# Watch-It-Board-2.net
KiCad netlist of a schematic drawn in EAGLE
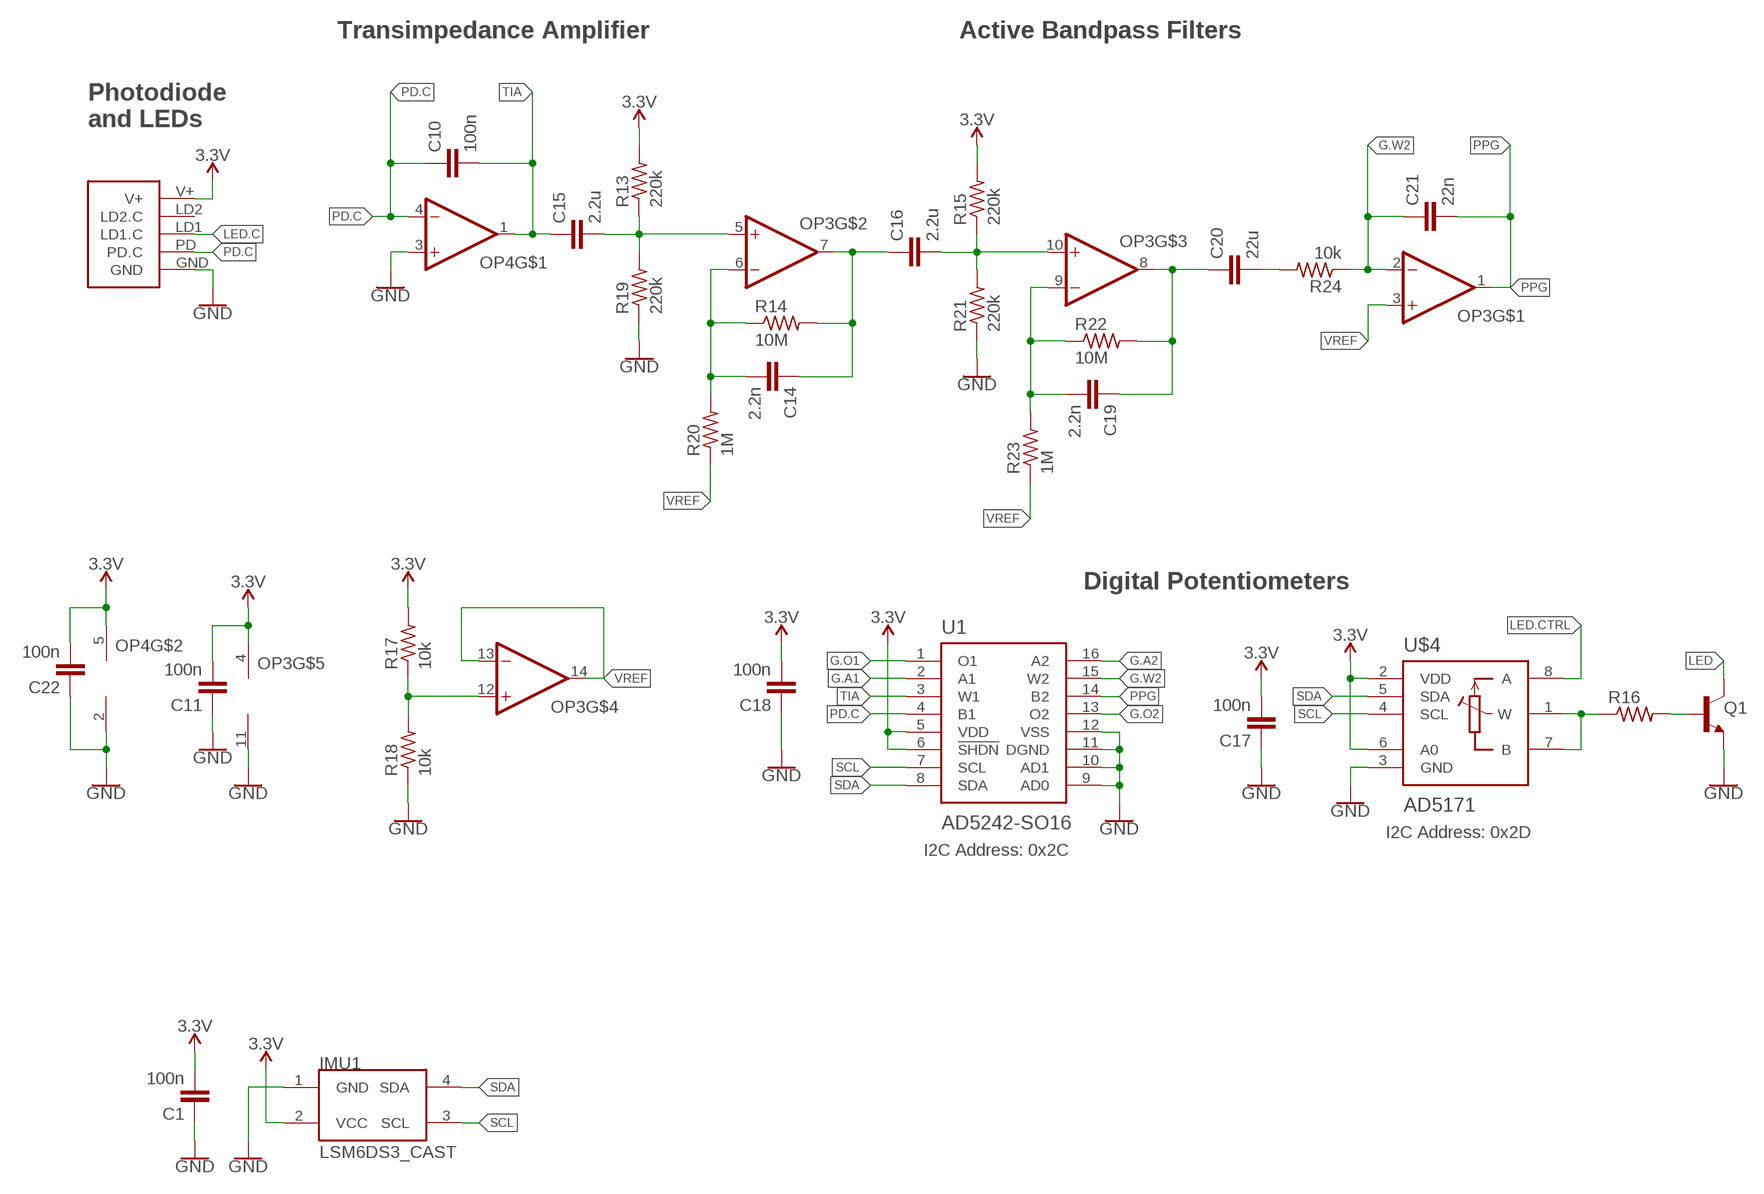
[diagram p0: schematic, sheet 1]

(export (version "E")
  (design (tool "Eeschema 10.0.6"))
  (components
    (comp (ref "C1")
      (value "100n")
      (footprint "eagle-import:C0603")
      (libsource (lib "eagle-import") (part "CAPACITOR0603"))
    )
    (comp (ref "C10")
      (value "100n")
      (footprint "eagle-import:C0603")
      (libsource (lib "eagle-import") (part "CAPACITOR0603"))
    )
    (comp (ref "C11")
      (value "100n")
      (footprint "eagle-import:C0603")
      (libsource (lib "eagle-import") (part "CAPACITOR0603"))
    )
    (comp (ref "C14")
      (value "2.2n")
      (footprint "eagle-import:C0603")
      (libsource (lib "eagle-import") (part "CAPACITOR0603"))
    )
    (comp (ref "C15")
      (value "2.2u")
      (footprint "eagle-import:C0603")
      (libsource (lib "eagle-import") (part "CAPACITOR0603"))
    )
    (comp (ref "C16")
      (value "2.2u")
      (footprint "eagle-import:C0603")
      (libsource (lib "eagle-import") (part "CAPACITOR0603"))
    )
    (comp (ref "C17")
      (value "100n")
      (footprint "eagle-import:C0603")
      (libsource (lib "eagle-import") (part "CAPACITOR0603"))
    )
    (comp (ref "C18")
      (value "100n")
      (footprint "eagle-import:C0603")
      (libsource (lib "eagle-import") (part "CAPACITOR0603"))
    )
    (comp (ref "C19")
      (value "2.2n")
      (footprint "eagle-import:C0603")
      (libsource (lib "eagle-import") (part "CAPACITOR0603"))
    )
    (comp (ref "C20")
      (value "22u")
      (footprint "eagle-import:C0603")
      (libsource (lib "eagle-import") (part "CAPACITOR0603"))
    )
    (comp (ref "C21")
      (value "22n")
      (footprint "eagle-import:C0603")
      (libsource (lib "eagle-import") (part "CAPACITOR0603"))
    )
    (comp (ref "C22")
      (value "100n")
      (footprint "eagle-import:C0603")
      (libsource (lib "eagle-import") (part "CAPACITOR0603"))
    )
    (comp (ref "IMU1")
      (value "LSM6DS3_CAST")
      (footprint "eagle-import:LSM6DS3_CAST")
      (libsource (lib "eagle-import") (part "LSM6DS3_CAST"))
    )
    (comp (ref "OP3")
      (value "OP-QUAD-SO14")
      (footprint "eagle-import:SO14")
      (libsource (lib "eagle-import") (part "OP-QUAD-SO14"))
    )
    (comp (ref "OP4")
      (value "OP-SINGLEOT")
      (footprint "eagle-import:SOT23-5")
      (libsource (lib "eagle-import") (part "OP-SINGLEOT"))
    )
    (comp (ref "Q1")
      (value "NPN-GENERIC")
      (footprint "eagle-import:SOT23-3")
      (libsource (lib "eagle-import") (part "NPN-GENERIC"))
    )
    (comp (ref "R13")
      (value "220k")
      (footprint "eagle-import:R0603")
      (libsource (lib "eagle-import") (part "RESISTOR0603"))
    )
    (comp (ref "R14")
      (value "10M")
      (footprint "eagle-import:R0603")
      (libsource (lib "eagle-import") (part "RESISTOR0603"))
    )
    (comp (ref "R15")
      (value "220k")
      (footprint "eagle-import:R0603")
      (libsource (lib "eagle-import") (part "RESISTOR0603"))
    )
    (comp (ref "R16")
      (value "RESISTOR0603")
      (footprint "eagle-import:R0603")
      (libsource (lib "eagle-import") (part "RESISTOR0603"))
    )
    (comp (ref "R17")
      (value "10k")
      (footprint "eagle-import:R0402")
      (libsource (lib "eagle-import") (part "RESISTOR0402"))
    )
    (comp (ref "R18")
      (value "10k")
      (footprint "eagle-import:R0402")
      (libsource (lib "eagle-import") (part "RESISTOR0402"))
    )
    (comp (ref "R19")
      (value "220k")
      (footprint "eagle-import:R0603")
      (libsource (lib "eagle-import") (part "RESISTOR0603"))
    )
    (comp (ref "R20")
      (value "1M")
      (footprint "eagle-import:R0603")
      (libsource (lib "eagle-import") (part "RESISTOR0603"))
    )
    (comp (ref "R21")
      (value "220k")
      (footprint "eagle-import:R0603")
      (libsource (lib "eagle-import") (part "RESISTOR0603"))
    )
    (comp (ref "R22")
      (value "10M")
      (footprint "eagle-import:R0603")
      (libsource (lib "eagle-import") (part "RESISTOR0603"))
    )
    (comp (ref "R23")
      (value "1M")
      (footprint "eagle-import:R0603")
      (libsource (lib "eagle-import") (part "RESISTOR0603"))
    )
    (comp (ref "R24")
      (value "10k")
      (footprint "eagle-import:R0603")
      (libsource (lib "eagle-import") (part "RESISTOR0603"))
    )
    (comp (ref "U$3")
      (value "PPG.MODULE.2")
      (footprint "eagle-import:PPG.MODULE.2")
      (libsource (lib "eagle-import") (part "PPG.MODULE.2"))
    )
    (comp (ref "U$4")
      (value "AD5171")
      (footprint "eagle-import:SOT-23-8")
      (libsource (lib "eagle-import") (part "AD5171"))
    )
    (comp (ref "U1")
      (value "AD5242-SO16")
      (footprint "eagle-import:SO16")
      (libsource (lib "eagle-import") (part "AD5242-SO16"))
    )
  )
  (nets
    (net (code "1") (name "3.3V") (class "Default")
      (node (ref "C1") (pin "2") (pinfunction "2_2") (pintype "passive"))
      (node (ref "C11") (pin "2") (pinfunction "2_2") (pintype "passive"))
      (node (ref "C17") (pin "2") (pinfunction "2_2") (pintype "passive"))
      (node (ref "C18") (pin "2") (pinfunction "2_2") (pintype "passive"))
      (node (ref "C22") (pin "2") (pinfunction "2_2") (pintype "passive"))
      (node (ref "IMU1") (pin "2") (pinfunction "VCC_2") (pintype "bidirectional"))
      (node (ref "OP3") (pin "4") (pinfunction "V+_4") (pintype "power_in"))
      (node (ref "OP4") (pin "5") (pinfunction "V+_5") (pintype "power_in"))
      (node (ref "R13") (pin "2") (pinfunction "2_2") (pintype "passive"))
      (node (ref "R15") (pin "2") (pinfunction "2_2") (pintype "passive"))
      (node (ref "R17") (pin "2") (pinfunction "2_2") (pintype "passive"))
      (node (ref "U$3") (pin "V+") (pinfunction "V+_V+") (pintype "bidirectional"))
      (node (ref "U$4") (pin "2") (pinfunction "VDD_2") (pintype "bidirectional"))
      (node (ref "U$4") (pin "6") (pinfunction "A0_6") (pintype "bidirectional"))
      (node (ref "U1") (pin "5") (pinfunction "VDD_5") (pintype "bidirectional"))
      (node (ref "U1") (pin "6") (pinfunction "~{SHDN}_6") (pintype "bidirectional"))
    )
    (net (code "2") (name "G.A1") (class "Default")
      (node (ref "U1") (pin "2") (pinfunction "A1_2") (pintype "bidirectional"))
    )
    (net (code "3") (name "G.A2") (class "Default")
      (node (ref "U1") (pin "16") (pinfunction "A2_16") (pintype "bidirectional"))
    )
    (net (code "4") (name "G.O1") (class "Default")
      (node (ref "U1") (pin "1") (pinfunction "O1_1") (pintype "bidirectional"))
    )
    (net (code "5") (name "G.O2") (class "Default")
      (node (ref "U1") (pin "13") (pinfunction "O2_13") (pintype "bidirectional"))
    )
    (net (code "6") (name "G.W2") (class "Default")
      (node (ref "C21") (pin "1") (pinfunction "1_1") (pintype "passive"))
      (node (ref "OP3") (pin "2") (pinfunction "-IN_2") (pintype "input"))
      (node (ref "R24") (pin "1") (pinfunction "1_1") (pintype "passive"))
      (node (ref "U1") (pin "15") (pinfunction "W2_15") (pintype "bidirectional"))
    )
    (net (code "7") (name "GND") (class "Default")
      (node (ref "C1") (pin "1") (pinfunction "1_1") (pintype "passive"))
      (node (ref "C11") (pin "1") (pinfunction "1_1") (pintype "passive"))
      (node (ref "C17") (pin "1") (pinfunction "1_1") (pintype "passive"))
      (node (ref "C18") (pin "1") (pinfunction "1_1") (pintype "passive"))
      (node (ref "C22") (pin "1") (pinfunction "1_1") (pintype "passive"))
      (node (ref "IMU1") (pin "1") (pinfunction "GND_1") (pintype "bidirectional"))
      (node (ref "OP3") (pin "11") (pinfunction "V-_11") (pintype "power_in"))
      (node (ref "OP4") (pin "2") (pinfunction "V-_2") (pintype "power_in"))
      (node (ref "OP4") (pin "3") (pinfunction "+IN_3") (pintype "input"))
      (node (ref "Q1") (pin "2") (pinfunction "E_2") (pintype "passive"))
      (node (ref "R18") (pin "1") (pinfunction "1_1") (pintype "passive"))
      (node (ref "R19") (pin "1") (pinfunction "1_1") (pintype "passive"))
      (node (ref "R21") (pin "1") (pinfunction "1_1") (pintype "passive"))
      (node (ref "U$3") (pin "GND") (pinfunction "GND_GND") (pintype "bidirectional"))
      (node (ref "U$4") (pin "3") (pinfunction "GND_3") (pintype "bidirectional"))
      (node (ref "U1") (pin "10") (pinfunction "AD1_10") (pintype "bidirectional"))
      (node (ref "U1") (pin "11") (pinfunction "DGND_11") (pintype "bidirectional"))
      (node (ref "U1") (pin "12") (pinfunction "VSS_12") (pintype "bidirectional"))
      (node (ref "U1") (pin "9") (pinfunction "AD0_9") (pintype "bidirectional"))
    )
    (net (code "8") (name "LED") (class "Default")
      (node (ref "Q1") (pin "3") (pinfunction "C_3") (pintype "passive"))
    )
    (net (code "9") (name "LED.C") (class "Default")
      (node (ref "U$3") (pin "LD1") (pinfunction "LD1.C_LD1") (pintype "bidirectional"))
    )
    (net (code "10") (name "LED.CTRL") (class "Default")
      (node (ref "U$4") (pin "8") (pinfunction "A_8") (pintype "bidirectional"))
    )
    (net (code "11") (name "Net-(C20-Pad2)") (class "Default")
      (node (ref "C20") (pin "2") (pinfunction "2_2") (pintype "passive"))
      (node (ref "R24") (pin "2") (pinfunction "2_2") (pintype "passive"))
    )
    (net (code "12") (name "Net-(OP3B-+IN)") (class "Default")
      (node (ref "C15") (pin "2") (pinfunction "2_2") (pintype "passive"))
      (node (ref "OP3") (pin "5") (pinfunction "+IN_5") (pintype "input"))
      (node (ref "R13") (pin "1") (pinfunction "1_1") (pintype "passive"))
      (node (ref "R19") (pin "2") (pinfunction "2_2") (pintype "passive"))
    )
    (net (code "13") (name "Net-(OP3B--IN)") (class "Default")
      (node (ref "C14") (pin "2") (pinfunction "2_2") (pintype "passive"))
      (node (ref "OP3") (pin "6") (pinfunction "-IN_6") (pintype "input"))
      (node (ref "R14") (pin "1") (pinfunction "1_1") (pintype "passive"))
      (node (ref "R20") (pin "2") (pinfunction "2_2") (pintype "passive"))
    )
    (net (code "14") (name "Net-(OP3B-OUT)") (class "Default")
      (node (ref "C14") (pin "1") (pinfunction "1_1") (pintype "passive"))
      (node (ref "C16") (pin "1") (pinfunction "1_1") (pintype "passive"))
      (node (ref "OP3") (pin "7") (pinfunction "OUT_7") (pintype "output"))
      (node (ref "R14") (pin "2") (pinfunction "2_2") (pintype "passive"))
    )
    (net (code "15") (name "Net-(OP3C-+IN)") (class "Default")
      (node (ref "C16") (pin "2") (pinfunction "2_2") (pintype "passive"))
      (node (ref "OP3") (pin "10") (pinfunction "+IN_10") (pintype "input"))
      (node (ref "R15") (pin "1") (pinfunction "1_1") (pintype "passive"))
      (node (ref "R21") (pin "2") (pinfunction "2_2") (pintype "passive"))
    )
    (net (code "16") (name "Net-(OP3C--IN)") (class "Default")
      (node (ref "C19") (pin "2") (pinfunction "2_2") (pintype "passive"))
      (node (ref "OP3") (pin "9") (pinfunction "-IN_9") (pintype "input"))
      (node (ref "R22") (pin "1") (pinfunction "1_1") (pintype "passive"))
      (node (ref "R23") (pin "2") (pinfunction "2_2") (pintype "passive"))
    )
    (net (code "17") (name "Net-(OP3C-OUT)") (class "Default")
      (node (ref "C19") (pin "1") (pinfunction "1_1") (pintype "passive"))
      (node (ref "C20") (pin "1") (pinfunction "1_1") (pintype "passive"))
      (node (ref "OP3") (pin "8") (pinfunction "OUT_8") (pintype "output"))
      (node (ref "R22") (pin "2") (pinfunction "2_2") (pintype "passive"))
    )
    (net (code "18") (name "Net-(OP3D-+IN)") (class "Default")
      (node (ref "OP3") (pin "12") (pinfunction "+IN_12") (pintype "input"))
      (node (ref "R17") (pin "1") (pinfunction "1_1") (pintype "passive"))
      (node (ref "R18") (pin "2") (pinfunction "2_2") (pintype "passive"))
    )
    (net (code "19") (name "Net-(Q1-B)") (class "Default")
      (node (ref "Q1") (pin "1") (pinfunction "B_1") (pintype "passive"))
      (node (ref "R16") (pin "2") (pinfunction "2_2") (pintype "passive"))
    )
    (net (code "20") (name "Net-(U$4-B)") (class "Default")
      (node (ref "R16") (pin "1") (pinfunction "1_1") (pintype "passive"))
      (node (ref "U$4") (pin "1") (pinfunction "W_1") (pintype "bidirectional"))
      (node (ref "U$4") (pin "7") (pinfunction "B_7") (pintype "bidirectional"))
    )
    (net (code "21") (name "PD.C") (class "Default")
      (node (ref "C10") (pin "1") (pinfunction "1_1") (pintype "passive"))
      (node (ref "OP4") (pin "4") (pinfunction "-IN_4") (pintype "input"))
      (node (ref "U$3") (pin "PD") (pinfunction "PD.C_PD") (pintype "bidirectional"))
      (node (ref "U1") (pin "4") (pinfunction "B1_4") (pintype "bidirectional"))
    )
    (net (code "22") (name "PPG") (class "Default")
      (node (ref "C21") (pin "2") (pinfunction "2_2") (pintype "passive"))
      (node (ref "OP3") (pin "1") (pinfunction "OUT_1") (pintype "output"))
      (node (ref "U1") (pin "14") (pinfunction "B2_14") (pintype "bidirectional"))
    )
    (net (code "23") (name "SCL") (class "Default")
      (node (ref "IMU1") (pin "3") (pinfunction "SCL_3") (pintype "bidirectional"))
      (node (ref "U$4") (pin "4") (pinfunction "SCL_4") (pintype "bidirectional"))
      (node (ref "U1") (pin "7") (pinfunction "SCL_7") (pintype "bidirectional"))
    )
    (net (code "24") (name "SDA") (class "Default")
      (node (ref "IMU1") (pin "4") (pinfunction "SDA_4") (pintype "bidirectional"))
      (node (ref "U$4") (pin "5") (pinfunction "SDA_5") (pintype "bidirectional"))
      (node (ref "U1") (pin "8") (pinfunction "SDA_8") (pintype "bidirectional"))
    )
    (net (code "25") (name "TIA") (class "Default")
      (node (ref "C10") (pin "2") (pinfunction "2_2") (pintype "passive"))
      (node (ref "C15") (pin "1") (pinfunction "1_1") (pintype "passive"))
      (node (ref "OP4") (pin "1") (pinfunction "OUT_1") (pintype "output"))
      (node (ref "U1") (pin "3") (pinfunction "W1_3") (pintype "bidirectional"))
    )
    (net (code "26") (name "VREF") (class "Default")
      (node (ref "OP3") (pin "13") (pinfunction "-IN_13") (pintype "input"))
      (node (ref "OP3") (pin "14") (pinfunction "OUT_14") (pintype "output"))
      (node (ref "OP3") (pin "3") (pinfunction "+IN_3") (pintype "input"))
      (node (ref "R20") (pin "1") (pinfunction "1_1") (pintype "passive"))
      (node (ref "R23") (pin "1") (pinfunction "1_1") (pintype "passive"))
    )
    (net (code "27") (name "unconnected-(U$3-LD2.C-PadLD2)") (class "Default")
      (node (ref "U$3") (pin "LD2") (pinfunction "LD2.C_LD2") (pintype "bidirectional"))
    )
  )
)
